# bsom-rs232-v002.net
KiCad netlist of a schematic drawn in EAGLE
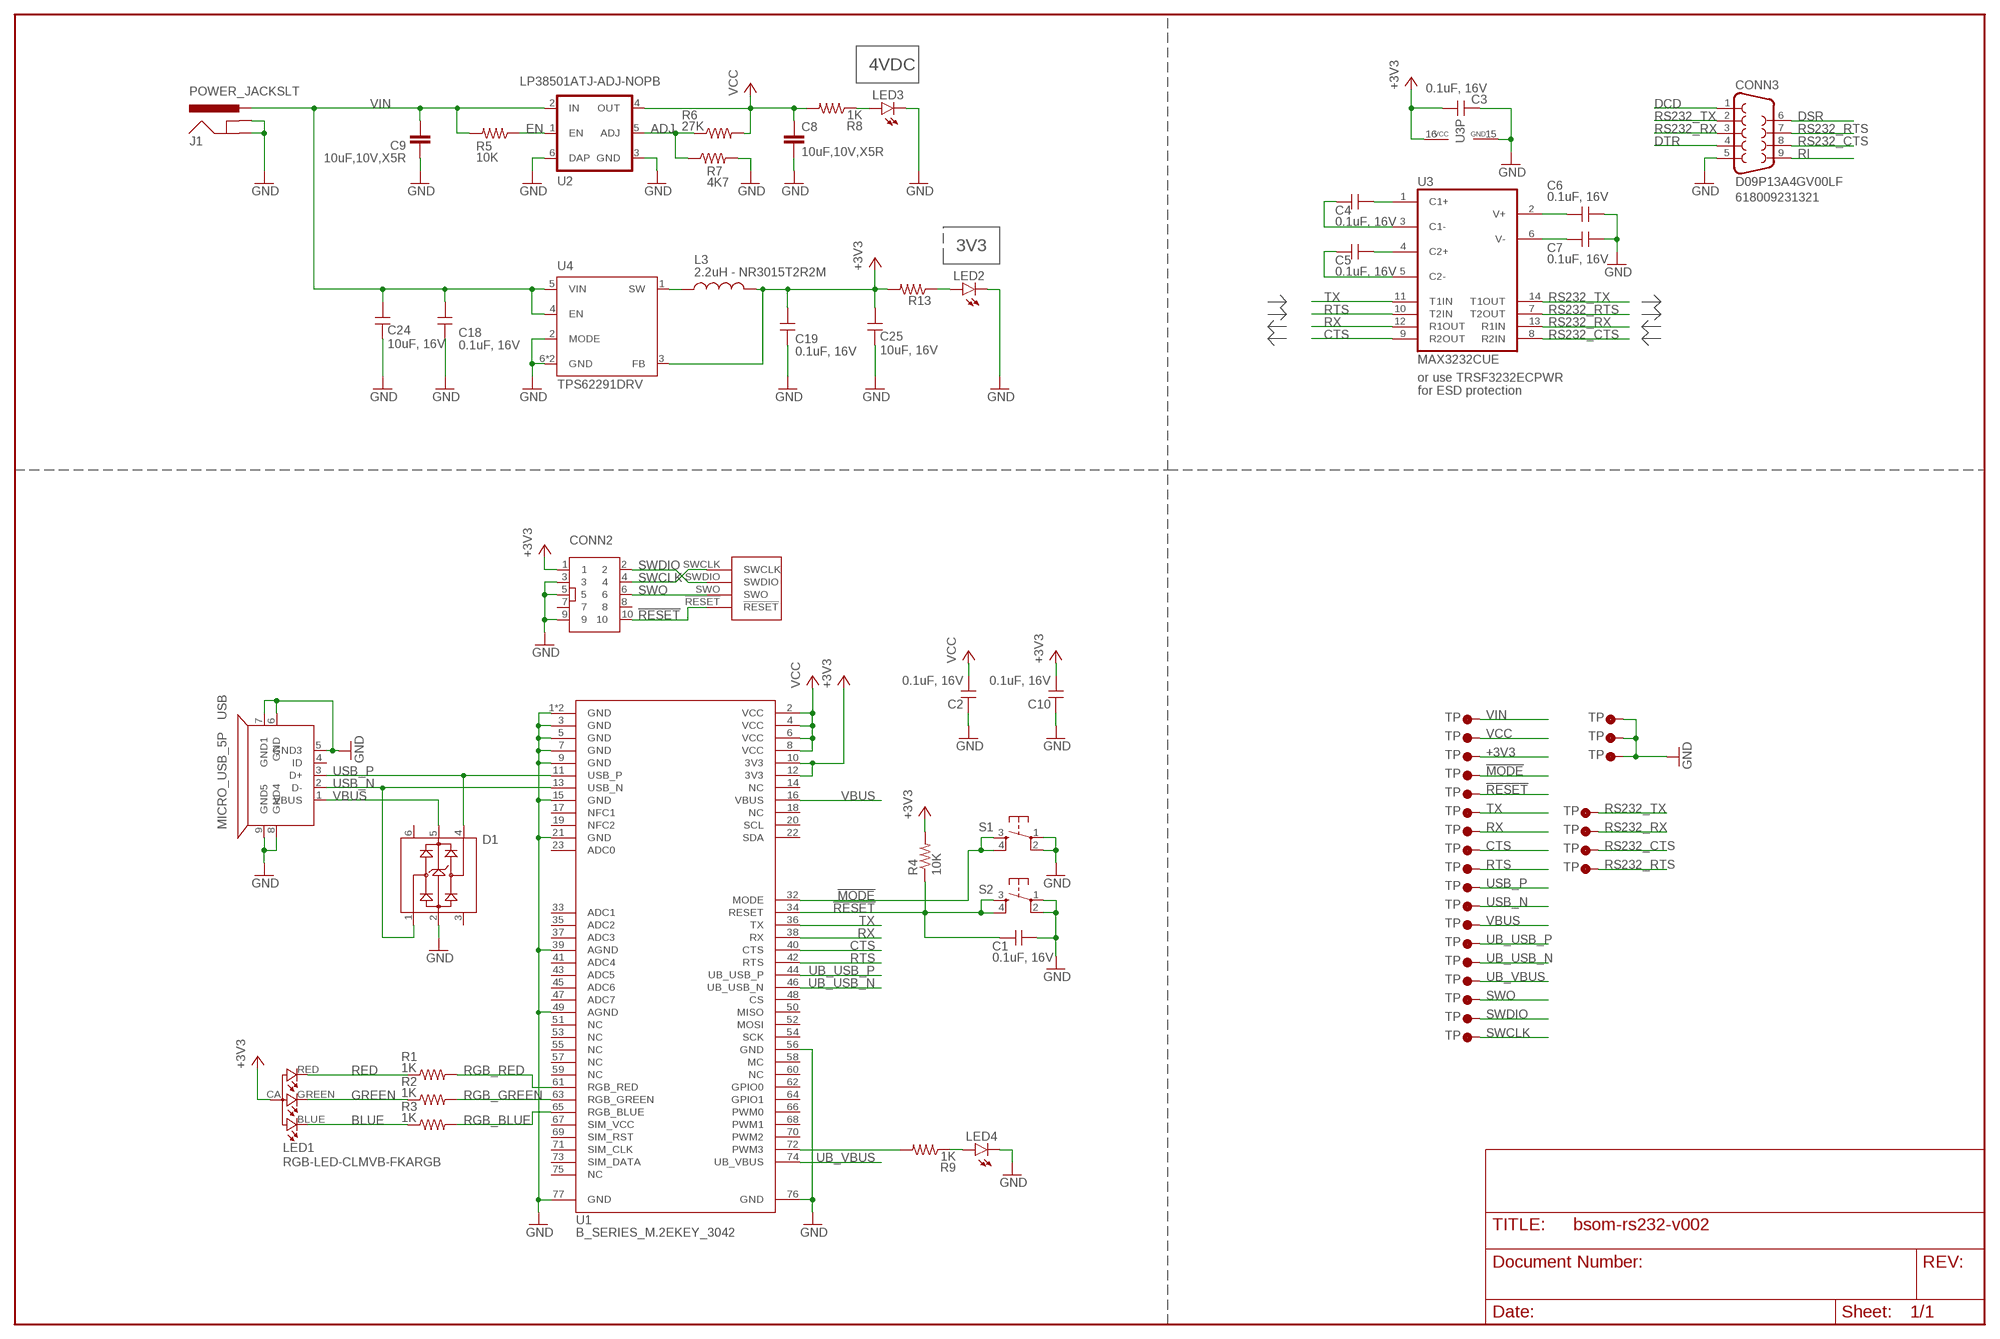
[diagram p0: schematic, sheet 1]

(export (version "E")
  (design (tool "Eeschema 10.0.6"))
  (components
    (comp (ref "C1")
      (value "0.1uF, 16V")
      (footprint "eagle-import:C0603_P")
      (libsource (lib "eagle-import") (part "CAP_06030.1UF_16V_"))
    )
    (comp (ref "C2")
      (value "0.1uF, 16V")
      (footprint "eagle-import:C0603_P")
      (libsource (lib "eagle-import") (part "CAP_06030.1UF_16V_"))
    )
    (comp (ref "C3")
      (value "0.1uF, 16V")
      (footprint "eagle-import:C0603_P")
      (libsource (lib "eagle-import") (part "CAP_06030.1UF_16V_"))
    )
    (comp (ref "C4")
      (value "0.1uF, 16V")
      (footprint "eagle-import:C0603_P")
      (libsource (lib "eagle-import") (part "CAP_06030.1UF_16V_"))
    )
    (comp (ref "C5")
      (value "0.1uF, 16V")
      (footprint "eagle-import:C0603_P")
      (libsource (lib "eagle-import") (part "CAP_06030.1UF_16V_"))
    )
    (comp (ref "C6")
      (value "0.1uF, 16V")
      (footprint "eagle-import:C0603_P")
      (libsource (lib "eagle-import") (part "CAP_06030.1UF_16V_"))
    )
    (comp (ref "C7")
      (value "0.1uF, 16V")
      (footprint "eagle-import:C0603_P")
      (libsource (lib "eagle-import") (part "CAP_06030.1UF_16V_"))
    )
    (comp (ref "C8")
      (value "10uF,10V,X5R")
      (footprint "eagle-import:C1206")
      (libsource (lib "eagle-import") (part "C-EUC1206"))
    )
    (comp (ref "C9")
      (value "10uF,10V,X5R")
      (footprint "eagle-import:C1206")
      (libsource (lib "eagle-import") (part "C-EUC1206"))
    )
    (comp (ref "C10")
      (value "0.1uF, 16V")
      (footprint "eagle-import:C0603_P")
      (libsource (lib "eagle-import") (part "CAP_06030.1UF_16V_"))
    )
    (comp (ref "C18")
      (value "0.1uF, 16V")
      (footprint "eagle-import:C0603_P")
      (libsource (lib "eagle-import") (part "CAP_06030.1UF_16V_"))
    )
    (comp (ref "C19")
      (value "0.1uF, 16V")
      (footprint "eagle-import:C0603_P")
      (libsource (lib "eagle-import") (part "CAP_06030.1UF_16V_"))
    )
    (comp (ref "C24")
      (value "10uF, 16V")
      (footprint "eagle-import:C0603_P")
      (libsource (lib "eagle-import") (part "CAP_060310UF_16V_"))
    )
    (comp (ref "C25")
      (value "10uF, 16V")
      (footprint "eagle-import:C0603_P")
      (libsource (lib "eagle-import") (part "CAP_060310UF_16V_"))
    )
    (comp (ref "CONN2")
      (value "CONN5X2")
      (footprint "eagle-import:CONN5X2_1.27")
      (fields (field (name "MFG") "KAWEEI") (field (name "MPN") "P6014A-M2GC-030-10"))
      (libsource (lib "eagle-import") (part "CONN5X2"))
    )
    (comp (ref "CONN3")
      (value "D09P13A4GV00LF")
      (footprint "eagle-import:F09HP")
      (libsource (lib "eagle-import") (part "F09HP"))
    )
    (comp (ref "D1")
      (value "MAX3207EAUT+T")
      (footprint "eagle-import:SOT23-6")
      (libsource (lib "eagle-import") (part "MAX3207EAUT+T"))
    )
    (comp (ref "J1")
      (value "POWER_JACKSLT")
      (footprint "eagle-import:POWER_JACK_SLOT")
      (libsource (lib "eagle-import") (part "POWER_JACKSLT"))
    )
    (comp (ref "L3")
      (value "2.2uH - NR3015T2R2M")
      (footprint "eagle-import:INDUCTOR-NR3015")
      (libsource (lib "eagle-import") (part "INDUCTOR-SPARKFUNNR3015T4R7M"))
    )
    (comp (ref "LED1")
      (value "RGB-LED-CLMVB-FKARGB")
      (footprint "eagle-import:PLCC4-2MM-RGB")
      (libsource (lib "eagle-import") (part "RGB-LED-CLMVB-FKARGB"))
    )
    (comp (ref "LED2")
      (value "LEDCHIP-LED0603")
      (footprint "eagle-import:CHIP-LED0603")
      (libsource (lib "eagle-import") (part "LEDCHIP-LED0603"))
    )
    (comp (ref "LED3")
      (value "LEDCHIP-LED0603")
      (footprint "eagle-import:CHIP-LED0603")
      (libsource (lib "eagle-import") (part "LEDCHIP-LED0603"))
    )
    (comp (ref "LED4")
      (value "LEDCHIP-LED0603")
      (footprint "eagle-import:CHIP-LED0603")
      (libsource (lib "eagle-import") (part "LEDCHIP-LED0603"))
    )
    (comp (ref "R1")
      (value "1K")
      (footprint "eagle-import:R0603_P")
      (libsource (lib "eagle-import") (part "RES_06031K_"))
    )
    (comp (ref "R2")
      (value "1K")
      (footprint "eagle-import:R0603_P")
      (libsource (lib "eagle-import") (part "RES_06031K_"))
    )
    (comp (ref "R3")
      (value "1K")
      (footprint "eagle-import:R0603_P")
      (libsource (lib "eagle-import") (part "RES_06031K_"))
    )
    (comp (ref "R4")
      (value "10K")
      (footprint "eagle-import:R0603_P")
      (libsource (lib "eagle-import") (part "RES_060310K_"))
    )
    (comp (ref "R5")
      (value "10K")
      (footprint "eagle-import:R0603_P")
      (libsource (lib "eagle-import") (part "RES_060310K_"))
    )
    (comp (ref "R6")
      (value "27K")
      (footprint "eagle-import:R0603_P")
      (libsource (lib "eagle-import") (part "RES_0603"))
    )
    (comp (ref "R7")
      (value "4K7")
      (footprint "eagle-import:R0603_P")
      (libsource (lib "eagle-import") (part "RES_0603"))
    )
    (comp (ref "R8")
      (value "1K")
      (footprint "eagle-import:R0603_P")
      (libsource (lib "eagle-import") (part "RES_06031K_"))
    )
    (comp (ref "R9")
      (value "1K")
      (footprint "eagle-import:R0603_P")
      (libsource (lib "eagle-import") (part "RES_06031K_"))
    )
    (comp (ref "R13")
      (value "RES_0603")
      (footprint "eagle-import:R0603_P")
      (libsource (lib "eagle-import") (part "RES_0603"))
    )
    (comp (ref "S1")
      (value "TAC_SWITCHSMD")
      (footprint "eagle-import:TACTILE_SWITCH_SMD")
      (libsource (lib "eagle-import") (part "TAC_SWITCHSMD"))
    )
    (comp (ref "S2")
      (value "TAC_SWITCHSMD")
      (footprint "eagle-import:TACTILE_SWITCH_SMD")
      (libsource (lib "eagle-import") (part "TAC_SWITCHSMD"))
    )
    (comp (ref "U$1")
      (value "TP5")
      (footprint "eagle-import:TP30_TOP")
      (libsource (lib "eagle-import") (part "TP5"))
    )
    (comp (ref "U$2")
      (value "TP5")
      (footprint "eagle-import:TP30_TOP")
      (libsource (lib "eagle-import") (part "TP5"))
    )
    (comp (ref "U$3")
      (value "TP5")
      (footprint "eagle-import:TP30_TOP")
      (libsource (lib "eagle-import") (part "TP5"))
    )
    (comp (ref "U$4")
      (value "TP5")
      (footprint "eagle-import:TP30_TOP")
      (libsource (lib "eagle-import") (part "TP5"))
    )
    (comp (ref "U$5")
      (value "TP5")
      (footprint "eagle-import:TP30_TOP")
      (libsource (lib "eagle-import") (part "TP5"))
    )
    (comp (ref "U$6")
      (value "TP5")
      (footprint "eagle-import:TP30_TOP")
      (libsource (lib "eagle-import") (part "TP5"))
    )
    (comp (ref "U$7")
      (value "TP5")
      (footprint "eagle-import:TP30_TOP")
      (libsource (lib "eagle-import") (part "TP5"))
    )
    (comp (ref "U$8")
      (value "TP5")
      (footprint "eagle-import:TP30_TOP")
      (libsource (lib "eagle-import") (part "TP5"))
    )
    (comp (ref "U$9")
      (value "TP5")
      (footprint "eagle-import:TP30_TOP")
      (libsource (lib "eagle-import") (part "TP5"))
    )
    (comp (ref "U$10")
      (value "TP5")
      (footprint "eagle-import:TP30_TOP")
      (libsource (lib "eagle-import") (part "TP5"))
    )
    (comp (ref "U$11")
      (value "TP5")
      (footprint "eagle-import:TP30_TOP")
      (libsource (lib "eagle-import") (part "TP5"))
    )
    (comp (ref "U$12")
      (value "TP5")
      (footprint "eagle-import:TP30_TOP")
      (libsource (lib "eagle-import") (part "TP5"))
    )
    (comp (ref "U$13")
      (value "TP5")
      (footprint "eagle-import:TP30_TOP")
      (libsource (lib "eagle-import") (part "TP5"))
    )
    (comp (ref "U$14")
      (value "TP5")
      (footprint "eagle-import:TP30_TOP")
      (libsource (lib "eagle-import") (part "TP5"))
    )
    (comp (ref "U$15")
      (value "TP5")
      (footprint "eagle-import:TP30_TOP")
      (libsource (lib "eagle-import") (part "TP5"))
    )
    (comp (ref "U$16")
      (value "TP5")
      (footprint "eagle-import:TP30_TOP")
      (libsource (lib "eagle-import") (part "TP5"))
    )
    (comp (ref "U$17")
      (value "TP5")
      (footprint "eagle-import:TP30_TOP")
      (libsource (lib "eagle-import") (part "TP5"))
    )
    (comp (ref "U$18")
      (value "TP5")
      (footprint "eagle-import:TP30_TOP")
      (libsource (lib "eagle-import") (part "TP5"))
    )
    (comp (ref "U$19")
      (value "TP5")
      (footprint "eagle-import:TP30_TOP")
      (libsource (lib "eagle-import") (part "TP5"))
    )
    (comp (ref "U$20")
      (value "TP5")
      (footprint "eagle-import:TP30_TOP")
      (libsource (lib "eagle-import") (part "TP5"))
    )
    (comp (ref "U$21")
      (value "TP5")
      (footprint "eagle-import:TP30_TOP")
      (libsource (lib "eagle-import") (part "TP5"))
    )
    (comp (ref "U$22")
      (value "TP5")
      (footprint "eagle-import:TP30_TOP")
      (libsource (lib "eagle-import") (part "TP5"))
    )
    (comp (ref "U$23")
      (value "TP5")
      (footprint "eagle-import:TP30_TOP")
      (libsource (lib "eagle-import") (part "TP5"))
    )
    (comp (ref "U$24")
      (value "TP5")
      (footprint "eagle-import:TP30_TOP")
      (libsource (lib "eagle-import") (part "TP5"))
    )
    (comp (ref "U$25")
      (value "TP5")
      (footprint "eagle-import:TP30_TOP")
      (libsource (lib "eagle-import") (part "TP5"))
    )
    (comp (ref "U1")
      (value "B_SERIES_M.2EKEY_3042")
      (footprint "eagle-import:PARTICLE_M.2EKEY")
      (libsource (lib "eagle-import") (part "B_SERIES_M.2EKEY_3042"))
    )
    (comp (ref "U2")
      (value "LP38501ATJ-ADJ-NOPB")
      (footprint "eagle-import:TI_NATIONAL_SEMICONDUCTOR_LP38501ATJ-ADJ-NOPB_0")
      (fields (field (name "MPN") "LP38501ATJ-ADJ/NOPB"))
      (libsource (lib "eagle-import") (part "LP38501ATJ-ADJ-NOPBTI_NATIONAL_SEMICONDUCTOR_LP38501ATJ-ADJ-NOPB_0_0"))
    )
    (comp (ref "U3")
      (value "MAX3232CUE")
      (footprint "eagle-import:TSSOP16")
      (fields (field (name "MF") "MAXIM") (field (name "MPN") "MAX3232CUE+"))
      (libsource (lib "eagle-import") (part "MAX3232UEC"))
    )
    (comp (ref "U4")
      (value "TPS62291DRV")
      (footprint "eagle-import:S-PWSON-N6")
      (libsource (lib "eagle-import") (part "TPS62291DRV"))
    )
    (comp (ref "USB")
      (value "MICRO_USB_5P")
      (footprint "eagle-import:MICRO_USB")
      (libsource (lib "eagle-import") (part "MICRO_USBMICRO_USB"))
    )
  )
  (nets
    (net (code "1") (name "+3V3") (class "Default")
      (node (ref "C10") (pin "1") (pinfunction "1_1") (pintype "bidirectional"))
      (node (ref "C19") (pin "1") (pinfunction "1_1") (pintype "bidirectional"))
      (node (ref "C25") (pin "1") (pinfunction "1_1") (pintype "bidirectional"))
      (node (ref "C3") (pin "2") (pinfunction "2_2") (pintype "bidirectional"))
      (node (ref "CONN2") (pin "1") (pinfunction "1_1") (pintype "bidirectional"))
      (node (ref "L3") (pin "2") (pinfunction "2_2") (pintype "passive"))
      (node (ref "LED1") (pin "CA") (pinfunction "1_CA") (pintype "passive"))
      (node (ref "R13") (pin "2") (pinfunction "2_2") (pintype "passive"))
      (node (ref "R4") (pin "2") (pinfunction "2_2") (pintype "passive"))
      (node (ref "U$2") (pin "P$1") (pinfunction "TP_P$1") (pintype "bidirectional"))
      (node (ref "U1") (pin "10") (pinfunction "3V3_10") (pintype "power_in"))
      (node (ref "U1") (pin "12") (pinfunction "3V3_12") (pintype "power_in"))
      (node (ref "U3") (pin "16") (pinfunction "VCC_16") (pintype "power_in"))
      (node (ref "U4") (pin "3") (pinfunction "FB_3") (pintype "bidirectional"))
    )
    (net (code "2") (name "/ADJ") (class "Default")
      (node (ref "R6") (pin "1") (pinfunction "1_1") (pintype "passive"))
      (node (ref "R7") (pin "1") (pinfunction "1_1") (pintype "passive"))
      (node (ref "U2") (pin "5") (pinfunction "ADJ_5") (pintype "input"))
    )
    (net (code "3") (name "/BLUE") (class "Default")
      (node (ref "LED1") (pin "BLUE") (pinfunction "2_BLUE") (pintype "passive"))
      (node (ref "R3") (pin "1") (pinfunction "1_1") (pintype "passive"))
    )
    (net (code "4") (name "/CTS") (class "Default")
      (node (ref "U$7") (pin "P$1") (pinfunction "TP_P$1") (pintype "bidirectional"))
      (node (ref "U1") (pin "40") (pinfunction "CTS_40") (pintype "bidirectional"))
      (node (ref "U3") (pin "9") (pinfunction "R2OUT_9") (pintype "output"))
    )
    (net (code "5") (name "/DCD") (class "Default")
      (node (ref "CONN3") (pin "1") (pinfunction "1_1") (pintype "passive"))
    )
    (net (code "6") (name "/DSR") (class "Default")
      (node (ref "CONN3") (pin "6") (pinfunction "6_6") (pintype "passive"))
    )
    (net (code "7") (name "/DTR") (class "Default")
      (node (ref "CONN3") (pin "4") (pinfunction "4_4") (pintype "passive"))
    )
    (net (code "8") (name "/EN") (class "Default")
      (node (ref "R5") (pin "1") (pinfunction "1_1") (pintype "passive"))
      (node (ref "U2") (pin "1") (pinfunction "EN_1") (pintype "input"))
    )
    (net (code "9") (name "/GREEN") (class "Default")
      (node (ref "LED1") (pin "GREEN") (pinfunction "3_GREEN") (pintype "passive"))
      (node (ref "R2") (pin "1") (pinfunction "1_1") (pintype "passive"))
    )
    (net (code "10") (name "/RED") (class "Default")
      (node (ref "LED1") (pin "RED") (pinfunction "4_RED") (pintype "passive"))
      (node (ref "R1") (pin "1") (pinfunction "1_1") (pintype "passive"))
    )
    (net (code "11") (name "/RGB_BLUE") (class "Default")
      (node (ref "R3") (pin "2") (pinfunction "2_2") (pintype "passive"))
      (node (ref "U1") (pin "65") (pinfunction "RGB_BLUE_65") (pintype "bidirectional"))
    )
    (net (code "12") (name "/RGB_GREEN") (class "Default")
      (node (ref "R2") (pin "2") (pinfunction "2_2") (pintype "passive"))
      (node (ref "U1") (pin "63") (pinfunction "RGB_GREEN_63") (pintype "bidirectional"))
    )
    (net (code "13") (name "/RGB_RED") (class "Default")
      (node (ref "R1") (pin "2") (pinfunction "2_2") (pintype "passive"))
      (node (ref "U1") (pin "61") (pinfunction "RGB_RED_61") (pintype "bidirectional"))
    )
    (net (code "14") (name "/RI") (class "Default")
      (node (ref "CONN3") (pin "9") (pinfunction "9_9") (pintype "passive"))
    )
    (net (code "15") (name "/RS232_CTS") (class "Default")
      (node (ref "CONN3") (pin "8") (pinfunction "8_8") (pintype "passive"))
      (node (ref "U$21") (pin "P$1") (pinfunction "TP_P$1") (pintype "bidirectional"))
      (node (ref "U3") (pin "8") (pinfunction "R2IN_8") (pintype "input"))
    )
    (net (code "16") (name "/RS232_RTS") (class "Default")
      (node (ref "CONN3") (pin "7") (pinfunction "7_7") (pintype "passive"))
      (node (ref "U$22") (pin "P$1") (pinfunction "TP_P$1") (pintype "bidirectional"))
      (node (ref "U3") (pin "7") (pinfunction "T2OUT_7") (pintype "output"))
    )
    (net (code "17") (name "/RS232_RX") (class "Default")
      (node (ref "CONN3") (pin "3") (pinfunction "3_3") (pintype "passive"))
      (node (ref "U$20") (pin "P$1") (pinfunction "TP_P$1") (pintype "bidirectional"))
      (node (ref "U3") (pin "13") (pinfunction "R1IN_13") (pintype "input"))
    )
    (net (code "18") (name "/RS232_TX") (class "Default")
      (node (ref "CONN3") (pin "2") (pinfunction "2_2") (pintype "passive"))
      (node (ref "U$19") (pin "P$1") (pinfunction "TP_P$1") (pintype "bidirectional"))
      (node (ref "U3") (pin "14") (pinfunction "T1OUT_14") (pintype "output"))
    )
    (net (code "19") (name "/RTS") (class "Default")
      (node (ref "U$8") (pin "P$1") (pinfunction "TP_P$1") (pintype "bidirectional"))
      (node (ref "U1") (pin "42") (pinfunction "RTS_42") (pintype "bidirectional"))
      (node (ref "U3") (pin "10") (pinfunction "T2IN_10") (pintype "input"))
    )
    (net (code "20") (name "/RX") (class "Default")
      (node (ref "U$6") (pin "P$1") (pinfunction "TP_P$1") (pintype "bidirectional"))
      (node (ref "U1") (pin "38") (pinfunction "RX_38") (pintype "bidirectional"))
      (node (ref "U3") (pin "12") (pinfunction "R1OUT_12") (pintype "output"))
    )
    (net (code "21") (name "/SIM_VCC") (class "Default")
      (node (ref "U1") (pin "67") (pinfunction "SIM_VCC_67") (pintype "power_in"))
    )
    (net (code "22") (name "/SWCLK") (class "Default")
      (node (ref "CONN2") (pin "4") (pinfunction "4_4") (pintype "bidirectional"))
      (node (ref "U$15") (pin "P$1") (pinfunction "TP_P$1") (pintype "bidirectional"))
      (node (ref "U1") (pin "SWCLK") (pinfunction "SWCLK_SWCLK") (pintype "power_in"))
    )
    (net (code "23") (name "/SWDIO") (class "Default")
      (node (ref "CONN2") (pin "2") (pinfunction "2_2") (pintype "bidirectional"))
      (node (ref "U$16") (pin "P$1") (pinfunction "TP_P$1") (pintype "bidirectional"))
      (node (ref "U1") (pin "SWDIO") (pinfunction "SWDIO_SWDIO") (pintype "power_in"))
    )
    (net (code "24") (name "/SWO") (class "Default")
      (node (ref "CONN2") (pin "6") (pinfunction "6_6") (pintype "bidirectional"))
      (node (ref "U$17") (pin "P$1") (pinfunction "TP_P$1") (pintype "bidirectional"))
      (node (ref "U1") (pin "SWO") (pinfunction "SWO_SWO") (pintype "power_in"))
    )
    (net (code "25") (name "/TX") (class "Default")
      (node (ref "U$5") (pin "P$1") (pinfunction "TP_P$1") (pintype "bidirectional"))
      (node (ref "U1") (pin "36") (pinfunction "TX_36") (pintype "bidirectional"))
      (node (ref "U3") (pin "11") (pinfunction "T1IN_11") (pintype "input"))
    )
    (net (code "26") (name "/UB_USB_N") (class "Default")
      (node (ref "U$13") (pin "P$1") (pinfunction "TP_P$1") (pintype "bidirectional"))
      (node (ref "U1") (pin "46") (pinfunction "UB_USB_N_46") (pintype "bidirectional"))
    )
    (net (code "27") (name "/UB_USB_P") (class "Default")
      (node (ref "U$12") (pin "P$1") (pinfunction "TP_P$1") (pintype "bidirectional"))
      (node (ref "U1") (pin "44") (pinfunction "UB_USB_P_44") (pintype "bidirectional"))
    )
    (net (code "28") (name "/UB_VBUS") (class "Default")
      (node (ref "U$18") (pin "P$1") (pinfunction "TP_P$1") (pintype "bidirectional"))
      (node (ref "U1") (pin "74") (pinfunction "UB_VBUS_74") (pintype "power_in"))
    )
    (net (code "29") (name "/USB_N") (class "Default")
      (node (ref "D1") (pin "1") (pinfunction "1_1") (pintype "bidirectional"))
      (node (ref "U$10") (pin "P$1") (pinfunction "TP_P$1") (pintype "bidirectional"))
      (node (ref "U1") (pin "13") (pinfunction "USB_N_13") (pintype "bidirectional"))
      (node (ref "USB") (pin "2") (pinfunction "D-_2") (pintype "bidirectional"))
    )
    (net (code "30") (name "/USB_P") (class "Default")
      (node (ref "D1") (pin "4") (pinfunction "4_4") (pintype "bidirectional"))
      (node (ref "U$9") (pin "P$1") (pinfunction "TP_P$1") (pintype "bidirectional"))
      (node (ref "U1") (pin "11") (pinfunction "USB_P_11") (pintype "bidirectional"))
      (node (ref "USB") (pin "3") (pinfunction "D+_3") (pintype "bidirectional"))
    )
    (net (code "31") (name "/VBUS") (class "Default")
      (node (ref "D1") (pin "5") (pinfunction "5_5") (pintype "bidirectional"))
      (node (ref "U$11") (pin "P$1") (pinfunction "TP_P$1") (pintype "bidirectional"))
      (node (ref "U1") (pin "16") (pinfunction "VBUS_16") (pintype "power_in"))
      (node (ref "USB") (pin "1") (pinfunction "VBUS_1") (pintype "bidirectional"))
    )
    (net (code "32") (name "/VIN") (class "Default")
      (node (ref "C18") (pin "1") (pinfunction "1_1") (pintype "bidirectional"))
      (node (ref "C24") (pin "1") (pinfunction "1_1") (pintype "bidirectional"))
      (node (ref "C9") (pin "1") (pinfunction "1_1") (pintype "passive"))
      (node (ref "J1") (pin "PWR") (pinfunction "PWR_PWR") (pintype "bidirectional"))
      (node (ref "R5") (pin "2") (pinfunction "2_2") (pintype "passive"))
      (node (ref "U$14") (pin "P$1") (pinfunction "TP_P$1") (pintype "bidirectional"))
      (node (ref "U2") (pin "2") (pinfunction "IN_2") (pintype "power_in"))
      (node (ref "U4") (pin "4") (pinfunction "EN_4") (pintype "bidirectional"))
      (node (ref "U4") (pin "5") (pinfunction "VIN_5") (pintype "bidirectional"))
    )
    (net (code "33") (name "/~{MODE}") (class "Default")
      (node (ref "S1") (pin "3") (pinfunction "3_3") (pintype "passive"))
      (node (ref "S1") (pin "4") (pinfunction "4_4") (pintype "passive"))
      (node (ref "U$3") (pin "P$1") (pinfunction "TP_P$1") (pintype "bidirectional"))
      (node (ref "U1") (pin "32") (pinfunction "MODE_32") (pintype "bidirectional"))
    )
    (net (code "34") (name "/~{RESET}") (class "Default")
      (node (ref "C1") (pin "1") (pinfunction "1_1") (pintype "bidirectional"))
      (node (ref "CONN2") (pin "10") (pinfunction "10_10") (pintype "bidirectional"))
      (node (ref "R4") (pin "1") (pinfunction "1_1") (pintype "passive"))
      (node (ref "S2") (pin "3") (pinfunction "3_3") (pintype "passive"))
      (node (ref "S2") (pin "4") (pinfunction "4_4") (pintype "passive"))
      (node (ref "U$4") (pin "P$1") (pinfunction "TP_P$1") (pintype "bidirectional"))
      (node (ref "U1") (pin "!RESET") (pinfunction "~{RESET}_!RESET") (pintype "power_in"))
      (node (ref "U1") (pin "34") (pinfunction "RESET_34") (pintype "bidirectional"))
    )
    (net (code "35") (name "GND") (class "Default")
      (node (ref "C1") (pin "2") (pinfunction "2_2") (pintype "bidirectional"))
      (node (ref "C10") (pin "2") (pinfunction "2_2") (pintype "bidirectional"))
      (node (ref "C18") (pin "2") (pinfunction "2_2") (pintype "bidirectional"))
      (node (ref "C19") (pin "2") (pinfunction "2_2") (pintype "bidirectional"))
      (node (ref "C2") (pin "2") (pinfunction "2_2") (pintype "bidirectional"))
      (node (ref "C24") (pin "2") (pinfunction "2_2") (pintype "bidirectional"))
      (node (ref "C25") (pin "2") (pinfunction "2_2") (pintype "bidirectional"))
      (node (ref "C3") (pin "1") (pinfunction "1_1") (pintype "bidirectional"))
      (node (ref "C6") (pin "1") (pinfunction "1_1") (pintype "bidirectional"))
      (node (ref "C7") (pin "1") (pinfunction "1_1") (pintype "bidirectional"))
      (node (ref "C8") (pin "2") (pinfunction "2_2") (pintype "passive"))
      (node (ref "C9") (pin "2") (pinfunction "2_2") (pintype "passive"))
      (node (ref "CONN2") (pin "3") (pinfunction "3_3") (pintype "bidirectional"))
      (node (ref "CONN2") (pin "5") (pinfunction "5_5") (pintype "bidirectional"))
      (node (ref "CONN2") (pin "9") (pinfunction "9_9") (pintype "bidirectional"))
      (node (ref "CONN3") (pin "5") (pinfunction "5_5") (pintype "passive"))
      (node (ref "D1") (pin "2") (pinfunction "2_2") (pintype "bidirectional"))
      (node (ref "J1") (pin "GND@1") (pinfunction "GNDBREAK_GND@1") (pintype "bidirectional"))
      (node (ref "J1") (pin "GND@2") (pinfunction "GND_GND@2") (pintype "bidirectional"))
      (node (ref "LED2") (pin "C") (pinfunction "C_C") (pintype "passive"))
      (node (ref "LED3") (pin "C") (pinfunction "C_C") (pintype "passive"))
      (node (ref "LED4") (pin "C") (pinfunction "C_C") (pintype "passive"))
      (node (ref "R7") (pin "2") (pinfunction "2_2") (pintype "passive"))
      (node (ref "S1") (pin "1") (pinfunction "1_1") (pintype "passive"))
      (node (ref "S1") (pin "2") (pinfunction "2_2") (pintype "passive"))
      (node (ref "S2") (pin "1") (pinfunction "1_1") (pintype "passive"))
      (node (ref "S2") (pin "2") (pinfunction "2_2") (pintype "passive"))
      (node (ref "U$23") (pin "P$1") (pinfunction "TP_P$1") (pintype "bidirectional"))
      (node (ref "U$24") (pin "P$1") (pinfunction "TP_P$1") (pintype "bidirectional"))
      (node (ref "U$25") (pin "P$1") (pinfunction "TP_P$1") (pintype "bidirectional"))
      (node (ref "U1") (pin "1") (pinfunction "GND_1") (pintype "power_in"))
      (node (ref "U1") (pin "15") (pinfunction "GND_15") (pintype "power_in"))
      (node (ref "U1") (pin "21") (pinfunction "GND_21") (pintype "power_in"))
      (node (ref "U1") (pin "3") (pinfunction "GND_3") (pintype "power_in"))
      (node (ref "U1") (pin "39") (pinfunction "AGND_39") (pintype "power_in"))
      (node (ref "U1") (pin "49") (pinfunction "AGND_49") (pintype "power_in"))
      (node (ref "U1") (pin "5") (pinfunction "GND_5") (pintype "power_in"))
      (node (ref "U1") (pin "56") (pinfunction "GND_56") (pintype "power_in"))
      (node (ref "U1") (pin "7") (pinfunction "GND_7") (pintype "power_in"))
      (node (ref "U1") (pin "76") (pinfunction "GND_76") (pintype "power_in"))
      (node (ref "U1") (pin "77") (pinfunction "GND_77") (pintype "power_in"))
      (node (ref "U1") (pin "9") (pinfunction "GND_9") (pintype "power_in"))
      (node (ref "U1") (pin "GND") (pinfunction "GND_GND") (pintype "power_in"))
      (node (ref "U2") (pin "3") (pinfunction "GND_3") (pintype "power_in"))
      (node (ref "U2") (pin "6") (pinfunction "DAP_6") (pintype "power_in"))
      (node (ref "U3") (pin "15") (pinfunction "GND_15") (pintype "power_in"))
      (node (ref "U4") (pin "2") (pinfunction "MODE_2") (pintype "bidirectional"))
      (node (ref "U4") (pin "6") (pinfunction "GND_6") (pintype "bidirectional"))
      (node (ref "U4") (pin "TP") (pinfunction "GND_TP") (pintype "bidirectional"))
      (node (ref "USB") (pin "5") (pinfunction "GND3_5") (pintype "bidirectional"))
      (node (ref "USB") (pin "6") (pinfunction "GND_6") (pintype "bidirectional"))
      (node (ref "USB") (pin "7") (pinfunction "GND1_7") (pintype "bidirectional"))
      (node (ref "USB") (pin "8") (pinfunction "GND4_8") (pintype "bidirectional"))
      (node (ref "USB") (pin "9") (pinfunction "GND5_9") (pintype "bidirectional"))
    )
    (net (code "36") (name "Net-(LED2-PadA)") (class "Default")
      (node (ref "LED2") (pin "A") (pinfunction "A_A") (pintype "passive"))
      (node (ref "R13") (pin "1") (pinfunction "1_1") (pintype "passive"))
    )
    (net (code "37") (name "Net-(LED3-PadA)") (class "Default")
      (node (ref "LED3") (pin "A") (pinfunction "A_A") (pintype "passive"))
      (node (ref "R8") (pin "1") (pinfunction "1_1") (pintype "passive"))
    )
    (net (code "38") (name "Net-(LED4-PadA)") (class "Default")
      (node (ref "LED4") (pin "A") (pinfunction "A_A") (pintype "passive"))
      (node (ref "R9") (pin "1") (pinfunction "1_1") (pintype "passive"))
    )
    (net (code "39") (name "Net-(U1B-PWM3)") (class "Default")
      (node (ref "R9") (pin "2") (pinfunction "2_2") (pintype "passive"))
      (node (ref "U1") (pin "72") (pinfunction "PWM3_72") (pintype "bidirectional"))
    )
    (net (code "40") (name "Net-(U3A-C1+)") (class "Default")
      (node (ref "C4") (pin "1") (pinfunction "1_1") (pintype "bidirectional"))
      (node (ref "U3") (pin "1") (pinfunction "C1+_1") (pintype "bidirectional"))
    )
    (net (code "41") (name "Net-(U3A-C1-)") (class "Default")
      (node (ref "C4") (pin "2") (pinfunction "2_2") (pintype "bidirectional"))
      (node (ref "U3") (pin "3") (pinfunction "C1-_3") (pintype "bidirectional"))
    )
    (net (code "42") (name "Net-(U3A-C2+)") (class "Default")
      (node (ref "C5") (pin "1") (pinfunction "1_1") (pintype "bidirectional"))
      (node (ref "U3") (pin "4") (pinfunction "C2+_4") (pintype "bidirectional"))
    )
    (net (code "43") (name "Net-(U3A-C2-)") (class "Default")
      (node (ref "C5") (pin "2") (pinfunction "2_2") (pintype "bidirectional"))
      (node (ref "U3") (pin "5") (pinfunction "C2-_5") (pintype "bidirectional"))
    )
    (net (code "44") (name "Net-(U3A-V+)") (class "Default")
      (node (ref "C6") (pin "2") (pinfunction "2_2") (pintype "bidirectional"))
      (node (ref "U3") (pin "2") (pinfunction "V+_2") (pintype "bidirectional"))
    )
    (net (code "45") (name "Net-(U3A-V-)") (class "Default")
      (node (ref "C7") (pin "2") (pinfunction "2_2") (pintype "bidirectional"))
      (node (ref "U3") (pin "6") (pinfunction "V-_6") (pintype "bidirectional"))
    )
    (net (code "46") (name "Net-(U4-SW)") (class "Default")
      (node (ref "L3") (pin "1") (pinfunction "1_1") (pintype "passive"))
      (node (ref "U4") (pin "1") (pinfunction "SW_1") (pintype "bidirectional"))
    )
    (net (code "47") (name "VCC") (class "Default")
      (node (ref "C2") (pin "1") (pinfunction "1_1") (pintype "bidirectional"))
      (node (ref "C8") (pin "1") (pinfunction "1_1") (pintype "passive"))
      (node (ref "R6") (pin "2") (pinfunction "2_2") (pintype "passive"))
      (node (ref "R8") (pin "2") (pinfunction "2_2") (pintype "passive"))
      (node (ref "U$1") (pin "P$1") (pinfunction "TP_P$1") (pintype "bidirectional"))
      (node (ref "U1") (pin "2") (pinfunction "VCC_2") (pintype "power_in"))
      (node (ref "U1") (pin "4") (pinfunction "VCC_4") (pintype "power_in"))
      (node (ref "U1") (pin "6") (pinfunction "VCC_6") (pintype "power_in"))
      (node (ref "U1") (pin "8") (pinfunction "VCC_8") (pintype "power_in"))
      (node (ref "U2") (pin "4") (pinfunction "OUT_4") (pintype "power_in"))
    )
    (net (code "48") (name "unconnected-(CONN2-Pad7)") (class "Default")
      (node (ref "CONN2") (pin "7") (pinfunction "7_7") (pintype "bidirectional"))
    )
    (net (code "49") (name "unconnected-(CONN2-Pad8)") (class "Default")
      (node (ref "CONN2") (pin "8") (pinfunction "8_8") (pintype "bidirectional"))
    )
    (net (code "50") (name "unconnected-(D1-Pad3)") (class "Default")
      (node (ref "D1") (pin "3") (pinfunction "3_3") (pintype "bidirectional"))
    )
    (net (code "51") (name "unconnected-(D1-Pad6)") (class "Default")
      (node (ref "D1") (pin "6") (pinfunction "6_6") (pintype "bidirectional"))
    )
    (net (code "52") (name "unconnected-(U1B-ADC0-Pad23)") (class "Default")
      (node (ref "U1") (pin "23") (pinfunction "ADC0_23") (pintype "bidirectional"))
    )
    (net (code "53") (name "unconnected-(U1B-ADC1-Pad33)") (class "Default")
      (node (ref "U1") (pin "33") (pinfunction "ADC1_33") (pintype "bidirectional"))
    )
    (net (code "54") (name "unconnected-(U1B-ADC2-Pad35)") (class "Default")
      (node (ref "U1") (pin "35") (pinfunction "ADC2_35") (pintype "bidirectional"))
    )
    (net (code "55") (name "unconnected-(U1B-ADC3-Pad37)") (class "Default")
      (node (ref "U1") (pin "37") (pinfunction "ADC3_37") (pintype "bidirectional"))
    )
    (net (code "56") (name "unconnected-(U1B-ADC4-Pad41)") (class "Default")
      (node (ref "U1") (pin "41") (pinfunction "ADC4_41") (pintype "bidirectional"))
    )
    (net (code "57") (name "unconnected-(U1B-ADC5-Pad43)") (class "Default")
      (node (ref "U1") (pin "43") (pinfunction "ADC5_43") (pintype "bidirectional"))
    )
    (net (code "58") (name "unconnected-(U1B-ADC6-Pad45)") (class "Default")
      (node (ref "U1") (pin "45") (pinfunction "ADC6_45") (pintype "bidirectional"))
    )
    (net (code "59") (name "unconnected-(U1B-ADC7-Pad47)") (class "Default")
      (node (ref "U1") (pin "47") (pinfunction "ADC7_47") (pintype "bidirectional"))
    )
    (net (code "60") (name "unconnected-(U1B-CS-Pad48)") (class "Default")
      (node (ref "U1") (pin "48") (pinfunction "CS_48") (pintype "bidirectional"))
    )
    (net (code "61") (name "unconnected-(U1B-GPIO0-Pad62)") (class "Default")
      (node (ref "U1") (pin "62") (pinfunction "GPIO0_62") (pintype "bidirectional"))
    )
    (net (code "62") (name "unconnected-(U1B-GPIO1-Pad64)") (class "Default")
      (node (ref "U1") (pin "64") (pinfunction "GPIO1_64") (pintype "bidirectional"))
    )
    (net (code "63") (name "unconnected-(U1B-MC-Pad58)") (class "Default")
      (node (ref "U1") (pin "58") (pinfunction "MC_58") (pintype "bidirectional"))
    )
    (net (code "64") (name "unconnected-(U1B-MISO-Pad50)") (class "Default")
      (node (ref "U1") (pin "50") (pinfunction "MISO_50") (pintype "bidirectional"))
    )
    (net (code "65") (name "unconnected-(U1B-MOSI-Pad52)") (class "Default")
      (node (ref "U1") (pin "52") (pinfunction "MOSI_52") (pintype "bidirectional"))
    )
    (net (code "66") (name "unconnected-(U1B-NC-Pad14)") (class "Default")
      (node (ref "U1") (pin "14") (pinfunction "NC_14") (pintype "bidirectional"))
    )
    (net (code "67") (name "unconnected-(U1B-NC-Pad18)") (class "Default")
      (node (ref "U1") (pin "18") (pinfunction "NC_18") (pintype "bidirectional"))
    )
    (net (code "68") (name "unconnected-(U1B-NC-Pad51)") (class "Default")
      (node (ref "U1") (pin "51") (pinfunction "NC_51") (pintype "bidirectional"))
    )
    (net (code "69") (name "unconnected-(U1B-NC-Pad53)") (class "Default")
      (node (ref "U1") (pin "53") (pinfunction "NC_53") (pintype "bidirectional"))
    )
    (net (code "70") (name "unconnected-(U1B-NC-Pad55)") (class "Default")
      (node (ref "U1") (pin "55") (pinfunction "NC_55") (pintype "bidirectional"))
    )
    (net (code "71") (name "unconnected-(U1B-NC-Pad57)") (class "Default")
      (node (ref "U1") (pin "57") (pinfunction "NC_57") (pintype "bidirectional"))
    )
    (net (code "72") (name "unconnected-(U1B-NC-Pad59)") (class "Default")
      (node (ref "U1") (pin "59") (pinfunction "NC_59") (pintype "bidirectional"))
    )
    (net (code "73") (name "unconnected-(U1B-NC-Pad60)") (class "Default")
      (node (ref "U1") (pin "60") (pinfunction "NC_60") (pintype "bidirectional"))
    )
    (net (code "74") (name "unconnected-(U1B-NC-Pad75)") (class "Default")
      (node (ref "U1") (pin "75") (pinfunction "NC_75") (pintype "bidirectional"))
    )
    (net (code "75") (name "unconnected-(U1B-NFC1-Pad17)") (class "Default")
      (node (ref "U1") (pin "17") (pinfunction "NFC1_17") (pintype "bidirectional"))
    )
    (net (code "76") (name "unconnected-(U1B-NFC2-Pad19)") (class "Default")
      (node (ref "U1") (pin "19") (pinfunction "NFC2_19") (pintype "bidirectional"))
    )
    (net (code "77") (name "unconnected-(U1B-PWM0-Pad66)") (class "Default")
      (node (ref "U1") (pin "66") (pinfunction "PWM0_66") (pintype "bidirectional"))
    )
    (net (code "78") (name "unconnected-(U1B-PWM1-Pad68)") (class "Default")
      (node (ref "U1") (pin "68") (pinfunction "PWM1_68") (pintype "bidirectional"))
    )
    (net (code "79") (name "unconnected-(U1B-PWM2-Pad70)") (class "Default")
      (node (ref "U1") (pin "70") (pinfunction "PWM2_70") (pintype "bidirectional"))
    )
    (net (code "80") (name "unconnected-(U1B-SCK-Pad54)") (class "Default")
      (node (ref "U1") (pin "54") (pinfunction "SCK_54") (pintype "bidirectional"))
    )
    (net (code "81") (name "unconnected-(U1B-SCL-Pad20)") (class "Default")
      (node (ref "U1") (pin "20") (pinfunction "SCL_20") (pintype "bidirectional"))
    )
    (net (code "82") (name "unconnected-(U1B-SDA-Pad22)") (class "Default")
      (node (ref "U1") (pin "22") (pinfunction "SDA_22") (pintype "bidirectional"))
    )
    (net (code "83") (name "unconnected-(U1B-SIM_CLK-Pad71)") (class "Default")
      (node (ref "U1") (pin "71") (pinfunction "SIM_CLK_71") (pintype "bidirectional"))
    )
    (net (code "84") (name "unconnected-(U1B-SIM_DATA-Pad73)") (class "Default")
      (node (ref "U1") (pin "73") (pinfunction "SIM_DATA_73") (pintype "bidirectional"))
    )
    (net (code "85") (name "unconnected-(U1B-SIM_RST-Pad69)") (class "Default")
      (node (ref "U1") (pin "69") (pinfunction "SIM_RST_69") (pintype "bidirectional"))
    )
    (net (code "86") (name "unconnected-(USB-ID-Pad4)") (class "Default")
      (node (ref "USB") (pin "4") (pinfunction "ID_4") (pintype "bidirectional"))
    )
  )
)
